# MCU_Controller.net
KiCad netlist of a schematic drawn in Altium Designer
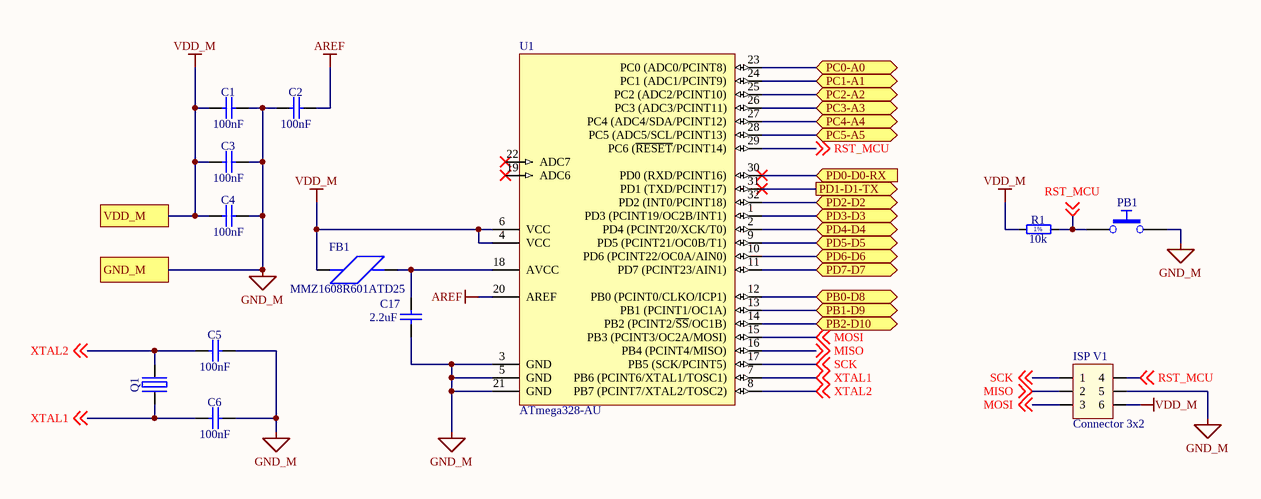
[diagram p0: MCU_Controller.SchDoc]

(export (version "E")
  (design (tool "Eeschema 10.0.6"))
  (components
    (comp (ref "C1")
      (value "100nF")
      (footprint "CAPC1608X87N")
      (description "Non-polarised capacitor")
      (fields
        (field (name "PART NUMBER") "CC0603_100NF_50V_10%_X7R")
        (field (name "VOLTAGE") "50V")
        (field (name "AUTHOR") "CERN DEM JLC")
      )
      (libsource (lib "Capacitors") (part "Capacitor - non polarized"))
    )
    (comp (ref "C2")
      (value "100nF")
      (footprint "CAPC1608X87N")
      (description "Non-polarised capacitor")
      (fields
        (field (name "PART NUMBER") "CC0603_100NF_50V_10%_X7R")
        (field (name "VOLTAGE") "50V")
        (field (name "AUTHOR") "CERN DEM JLC")
      )
      (libsource (lib "Capacitors") (part "Capacitor - non polarized"))
    )
    (comp (ref "C3")
      (value "100nF")
      (footprint "CAPC1608X87N")
      (description "Non-polarised capacitor")
      (fields
        (field (name "PART NUMBER") "CC0603_100NF_50V_10%_X7R")
        (field (name "VOLTAGE") "50V")
        (field (name "AUTHOR") "CERN DEM JLC")
      )
      (libsource (lib "Capacitors") (part "Capacitor - non polarized"))
    )
    (comp (ref "C4")
      (value "100nF")
      (footprint "CAPC1608X87N")
      (description "Non-polarised capacitor")
      (fields
        (field (name "PART NUMBER") "CC0603_100NF_50V_10%_X7R")
        (field (name "VOLTAGE") "50V")
        (field (name "AUTHOR") "CERN DEM JLC")
      )
      (libsource (lib "Capacitors") (part "Capacitor - non polarized"))
    )
    (comp (ref "C5")
      (value "100nF")
      (footprint "CAPC1608X87N")
      (description "Non-polarised capacitor")
      (fields
        (field (name "PART NUMBER") "CC0603_22PF_50V_5%_NP0")
        (field (name "VOLTAGE") "50V")
        (field (name "AUTHOR") "CERN DEM JLC")
      )
      (libsource (lib "Capacitors") (part "Capacitor - non polarized"))
    )
    (comp (ref "C6")
      (value "100nF")
      (footprint "CAPC1608X87N")
      (description "Non-polarised capacitor")
      (fields
        (field (name "PART NUMBER") "CC0603_22PF_50V_5%_NP0")
        (field (name "VOLTAGE") "50V")
        (field (name "AUTHOR") "CERN DEM JLC")
      )
      (libsource (lib "Capacitors") (part "Capacitor - non polarized"))
    )
    (comp (ref "C17")
      (value "2.2uF")
      (footprint "CAPC1608X87N")
      (description "Non-polarised capacitor")
      (fields
        (field (name "PART NUMBER") "CC0603_2.2UF_16V_10%_X5R")
        (field (name "VOLTAGE") "16V")
        (field (name "AUTHOR") "CERN DEM JLC")
      )
      (libsource (lib "Capacitors") (part "Capacitor - non polarized"))
    )
    (comp (ref "FB1")
      (value "Ferrite bead Case 0603")
      (footprint "Chip_0603")
      (fields (field (name "MANUFACTURER PART NUMBER") "MMZ1608R601ATD25"))
      (libsource (lib "Schlib1") (part "FERRITE_0603"))
    )
    (comp (ref "ISP V1")
      (value "Connector 3x2")
      (footprint "JP3x2")
      (libsource (lib "syhaunguyen") (part "JP3x2"))
    )
    (comp (ref "PB1")
      (value "Push Button")
      (footprint "PB_TYCO_FSMSM")
      (description "Push-Button Switch SPDT")
      (fields
        (field (name "PART NUMBER") "PB_TYCO_FSMSM")
        (field (name "MANUFACTURER") "TYCO ELECTRONICS")
        (field (name "AUTHOR") "CERN DEM JLC")
      )
      (libsource (lib "alib_pnphien") (part "PB SPST 1NO-2NO"))
    )
    (comp (ref "Q1")
      (value "20MHz")
      (footprint "XTAL_HC-49/U")
      (description "Quartz Crystal")
      (fields
        (field (name "PART NUMBER") "XTAL_20MHZ_AEL_HC-49/U")
        (field (name "MANUFACTURER") "AEL CRYSTALS")
        (field (name "AUTHOR") "CERN DEM JMW")
      )
      (libsource (lib "ICs And Semiconductors") (part "Quartz Crystal"))
    )
    (comp (ref "R1")
      (value "10k")
      (footprint "RESC1608X55N")
      (description "Resistor - 1%")
      (fields
        (field (name "PART NUMBER") "R0603_10K_1%_0.1W_100PPM")
        (field (name "POWER") "0.1W")
        (field (name "AUTHOR") "CERN DEM JLC")
      )
      (libsource (lib "Resistors") (part "Resistor - 1%"))
    )
    (comp (ref "U1")
      (value "ATmega328-AU")
      (footprint "32A_ATM-M")
      (fields (field (name "PUBLISHER") "Altium Limited"))
      (libsource (lib "alib_pnphien") (part "ATmega328-AU"))
    )
  )
  (nets
    (net (code "1") (name "/PB0-D8") (class "Default")
      (node (ref "U1") (pin "12") (pinfunction "PB0_(PCINT0/CLKO/ICP1)_12") (pintype "bidirectional"))
    )
    (net (code "2") (name "/PB1-D9") (class "Default")
      (node (ref "U1") (pin "13") (pinfunction "PB1_(PCINT1/OC1A)_13") (pintype "bidirectional"))
    )
    (net (code "3") (name "/PB2-D10") (class "Default")
      (node (ref "U1") (pin "14") (pinfunction "PB2_(PCINT2/~{SS}/OC1B)_14") (pintype "bidirectional"))
    )
    (net (code "4") (name "/PC0-A0") (class "Default")
      (node (ref "U1") (pin "23") (pinfunction "PC0_(ADC0/PCINT8)_23") (pintype "bidirectional"))
    )
    (net (code "5") (name "/PC1-A1") (class "Default")
      (node (ref "U1") (pin "24") (pinfunction "PC1_(ADC1/PCINT9)_24") (pintype "bidirectional"))
    )
    (net (code "6") (name "/PC2-A2") (class "Default")
      (node (ref "U1") (pin "25") (pinfunction "PC2_(ADC2/PCINT10)_25") (pintype "bidirectional"))
    )
    (net (code "7") (name "/PC3-A3") (class "Default")
      (node (ref "U1") (pin "26") (pinfunction "PC3_(ADC3/PCINT11)_26") (pintype "bidirectional"))
    )
    (net (code "8") (name "/PC4-A4") (class "Default")
      (node (ref "U1") (pin "27") (pinfunction "PC4_(ADC4/SDA/PCINT12)_27") (pintype "bidirectional"))
    )
    (net (code "9") (name "/PC5-A5") (class "Default")
      (node (ref "U1") (pin "28") (pinfunction "PC5_(ADC5/SCL/PCINT13)_28") (pintype "bidirectional"))
    )
    (net (code "10") (name "/PD0-D0-RX") (class "Default")
      (node (ref "U1") (pin "30") (pinfunction "PD0_(RXD/PCINT16)_30") (pintype "bidirectional+no_connect"))
    )
    (net (code "11") (name "/PD1-D1-TX") (class "Default")
      (node (ref "U1") (pin "31") (pinfunction "PD1_(TXD/PCINT17)_31") (pintype "bidirectional+no_connect"))
    )
    (net (code "12") (name "/PD2-D2") (class "Default")
      (node (ref "U1") (pin "32") (pinfunction "PD2_(INT0/PCINT18)_32") (pintype "bidirectional"))
    )
    (net (code "13") (name "/PD3-D3") (class "Default")
      (node (ref "U1") (pin "1") (pinfunction "PD3_(PCINT19/OC2B/INT1)_1") (pintype "bidirectional"))
    )
    (net (code "14") (name "/PD4-D4") (class "Default")
      (node (ref "U1") (pin "2") (pinfunction "PD4_(PCINT20/XCK/T0)_2") (pintype "bidirectional"))
    )
    (net (code "15") (name "/PD5-D5") (class "Default")
      (node (ref "U1") (pin "9") (pinfunction "PD5_(PCINT21/OC0B/T1)_9") (pintype "bidirectional"))
    )
    (net (code "16") (name "/PD6-D6") (class "Default")
      (node (ref "U1") (pin "10") (pinfunction "PD6_(PCINT22/OC0A/AIN0)_10") (pintype "bidirectional"))
    )
    (net (code "17") (name "/PD7-D7") (class "Default")
      (node (ref "U1") (pin "11") (pinfunction "PD7_(PCINT23/AIN1)_11") (pintype "bidirectional"))
    )
    (net (code "18") (name "AREF") (class "Default")
      (node (ref "C2") (pin "2") (pinfunction "2_2") (pintype "passive"))
      (node (ref "U1") (pin "20") (pinfunction "AREF_20") (pintype "passive"))
    )
    (net (code "19") (name "GND_M") (class "Default")
      (node (ref "C1") (pin "2") (pinfunction "2_2") (pintype "passive"))
      (node (ref "C17") (pin "1") (pinfunction "1_1") (pintype "passive"))
      (node (ref "C2") (pin "1") (pinfunction "1_1") (pintype "passive"))
      (node (ref "C3") (pin "2") (pinfunction "2_2") (pintype "passive"))
      (node (ref "C4") (pin "2") (pinfunction "2_2") (pintype "passive"))
      (node (ref "C5") (pin "2") (pinfunction "2_2") (pintype "passive"))
      (node (ref "C6") (pin "2") (pinfunction "2_2") (pintype "passive"))
      (node (ref "ISP V1") (pin "5") (pinfunction "5_5") (pintype "passive"))
      (node (ref "PB1") (pin "2") (pinfunction "2_2") (pintype "passive"))
      (node (ref "U1") (pin "21") (pinfunction "GND_21") (pintype "power_in"))
      (node (ref "U1") (pin "3") (pinfunction "GND_3") (pintype "power_in"))
      (node (ref "U1") (pin "5") (pinfunction "GND_5") (pintype "power_in"))
    )
    (net (code "20") (name "MISO") (class "Default")
      (node (ref "ISP V1") (pin "2") (pinfunction "2_2") (pintype "passive"))
      (node (ref "U1") (pin "16") (pinfunction "PB4_(PCINT4/MISO)_16") (pintype "bidirectional"))
    )
    (net (code "21") (name "MOSI") (class "Default")
      (node (ref "ISP V1") (pin "3") (pinfunction "3_3") (pintype "passive"))
      (node (ref "U1") (pin "15") (pinfunction "PB3_(PCINT3/OC2A/MOSI)_15") (pintype "bidirectional"))
    )
    (net (code "22") (name "Net-(U1-AVCC)") (class "Default")
      (node (ref "C17") (pin "2") (pinfunction "2_2") (pintype "passive"))
      (node (ref "FB1") (pin "2") (pinfunction "2_2") (pintype "passive"))
      (node (ref "U1") (pin "18") (pinfunction "AVCC_18") (pintype "power_in"))
    )
    (net (code "23") (name "RST_MCU") (class "Default")
      (node (ref "ISP V1") (pin "4") (pinfunction "4_4") (pintype "passive"))
      (node (ref "PB1") (pin "1") (pinfunction "1_1") (pintype "passive"))
      (node (ref "R1") (pin "2") (pinfunction "2_2") (pintype "passive"))
      (node (ref "U1") (pin "29") (pinfunction "PC6_(~{RESET}/PCINT14)_29") (pintype "bidirectional"))
    )
    (net (code "24") (name "SCK") (class "Default")
      (node (ref "ISP V1") (pin "1") (pinfunction "1_1") (pintype "passive"))
      (node (ref "U1") (pin "17") (pinfunction "PB5_(SCK/PCINT5)_17") (pintype "bidirectional"))
    )
    (net (code "25") (name "VDD_M") (class "Default")
      (node (ref "C1") (pin "1") (pinfunction "1_1") (pintype "passive"))
      (node (ref "C3") (pin "1") (pinfunction "1_1") (pintype "passive"))
      (node (ref "C4") (pin "1") (pinfunction "1_1") (pintype "passive"))
      (node (ref "FB1") (pin "1") (pinfunction "1_1") (pintype "passive"))
      (node (ref "ISP V1") (pin "6") (pinfunction "6_6") (pintype "passive"))
      (node (ref "R1") (pin "1") (pinfunction "1_1") (pintype "passive"))
      (node (ref "U1") (pin "4") (pinfunction "VCC_4") (pintype "power_in"))
      (node (ref "U1") (pin "6") (pinfunction "VCC_6") (pintype "power_in"))
    )
    (net (code "26") (name "XTAL1") (class "Default")
      (node (ref "C6") (pin "1") (pinfunction "1_1") (pintype "passive"))
      (node (ref "Q1") (pin "1") (pinfunction "OSC1_1") (pintype "passive"))
      (node (ref "U1") (pin "7") (pinfunction "PB6_(PCINT6/XTAL1/TOSC1)_7") (pintype "bidirectional"))
    )
    (net (code "27") (name "XTAL2") (class "Default")
      (node (ref "C5") (pin "1") (pinfunction "1_1") (pintype "passive"))
      (node (ref "Q1") (pin "2") (pinfunction "OSC2_2") (pintype "passive"))
      (node (ref "U1") (pin "8") (pinfunction "PB7_(PCINT7/XTAL2/TOSC2)_8") (pintype "bidirectional"))
    )
    (net (code "28") (name "unconnected-(U1-ADC6-Pad19)") (class "Default")
      (node (ref "U1") (pin "19") (pinfunction "ADC6_19") (pintype "input+no_connect"))
    )
    (net (code "29") (name "unconnected-(U1-ADC7-Pad22)") (class "Default")
      (node (ref "U1") (pin "22") (pinfunction "ADC7_22") (pintype "input+no_connect"))
    )
  )
)
